# 09F-01.net
KiCad netlist of a schematic drawn in EAGLE
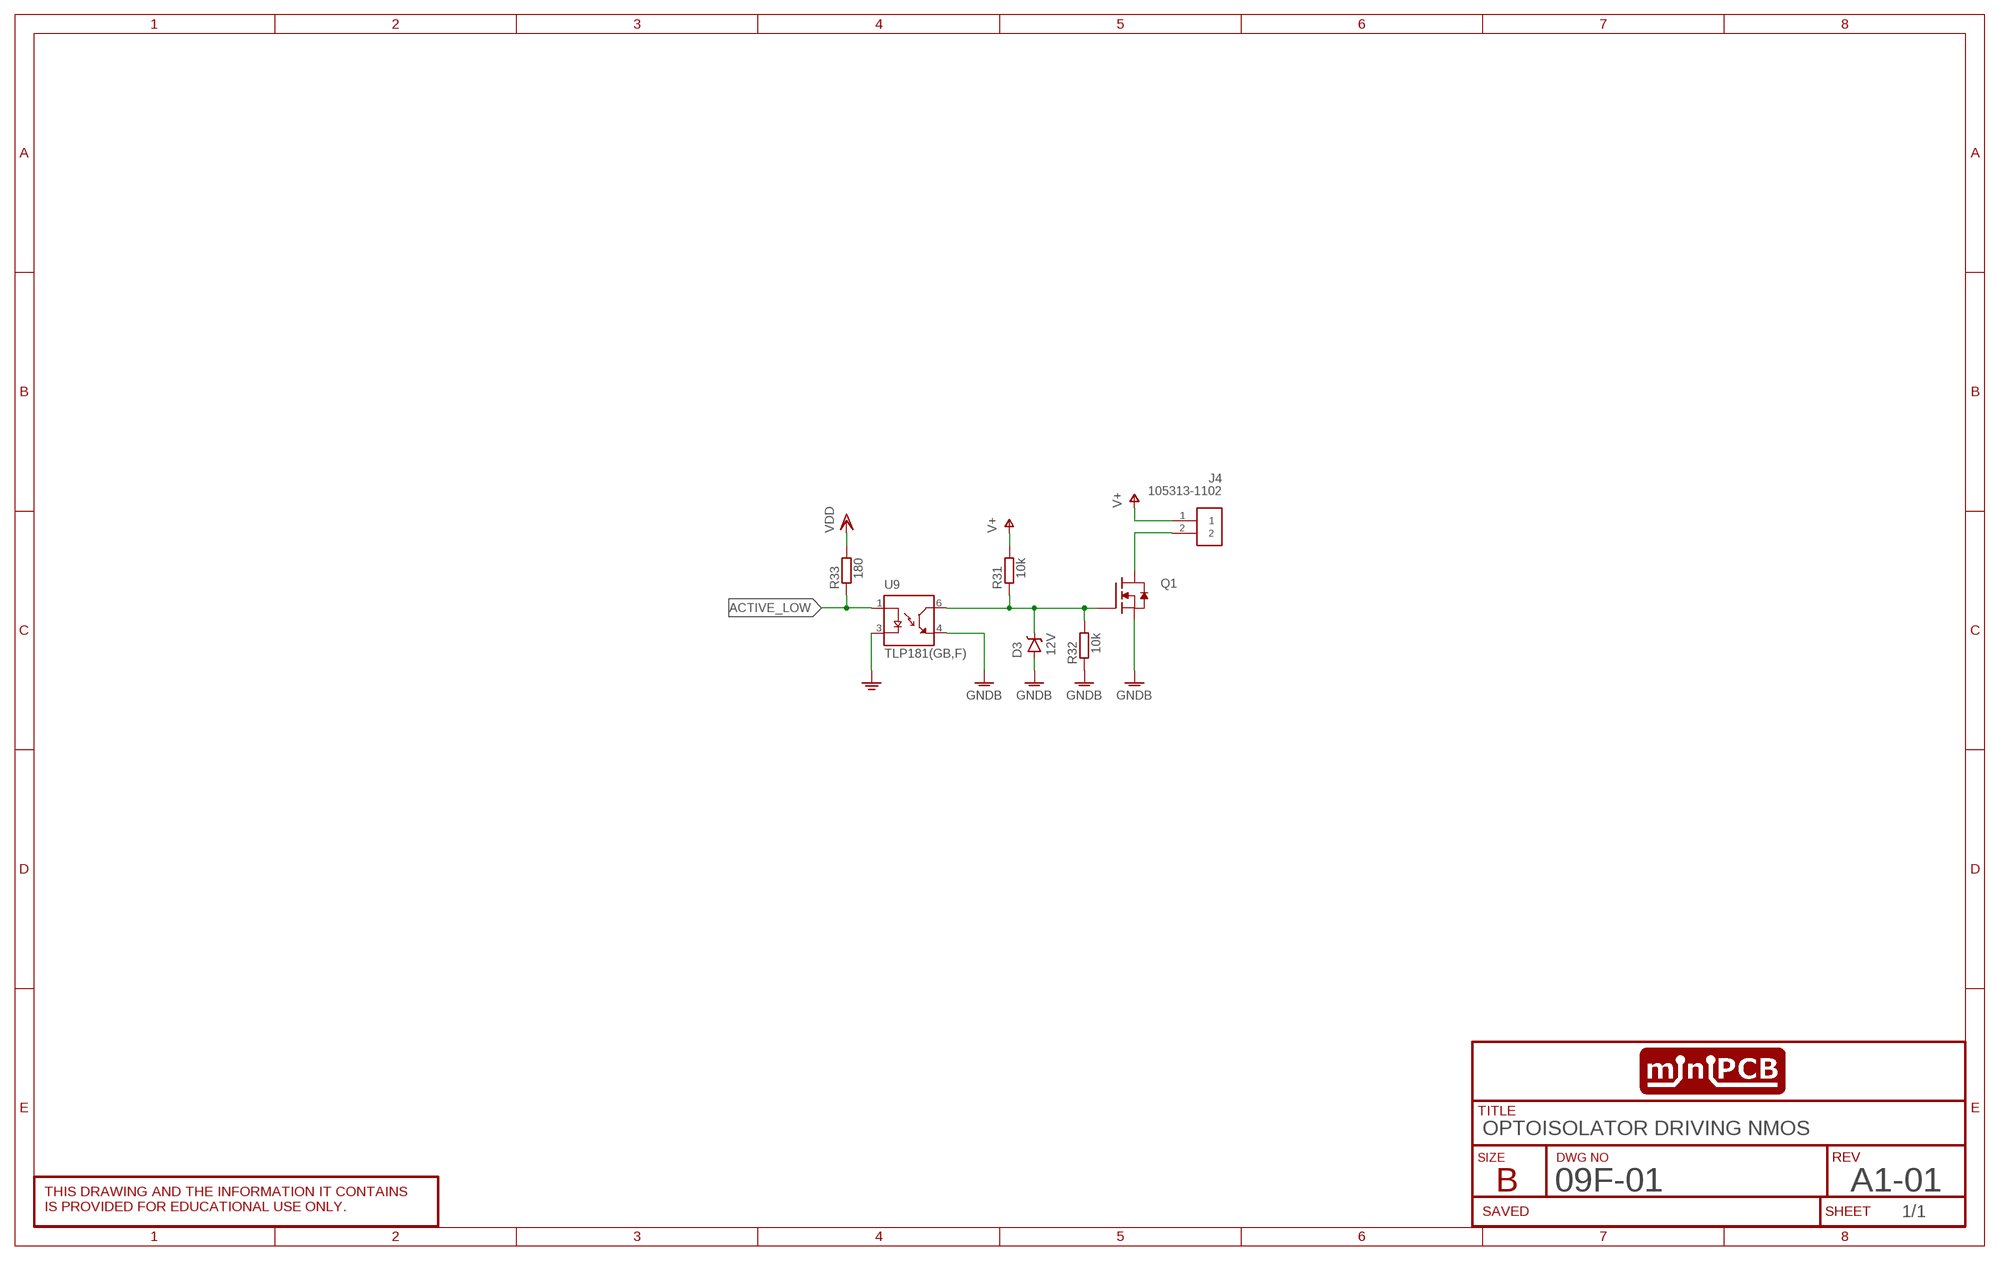
[diagram p0: schematic, sheet 1]

(export (version "E")
  (design (tool "Eeschema 10.0.6"))
  (components
    (comp (ref "D3")
      (value "12V")
      (footprint "eagle-import:SOT23")
      (libsource (lib "eagle-import") (part "ZENERSOT23"))
    )
    (comp (ref "J4")
      (value "105313-1102")
      (footprint "eagle-import:PINS_2-NANOFIT-H")
      (libsource (lib "eagle-import") (part "PINS_2-NANOFIT-105313-1102"))
    )
    (comp (ref "Q1")
      (value "MOSFET-NDPAK")
      (footprint "eagle-import:DPACK")
      (libsource (lib "eagle-import") (part "MOSFET-NDPAK"))
    )
    (comp (ref "R31")
      (value "10k")
      (footprint "eagle-import:R0805")
      (libsource (lib "eagle-import") (part "RESISTORSMD"))
    )
    (comp (ref "R32")
      (value "10k")
      (footprint "eagle-import:R0805")
      (libsource (lib "eagle-import") (part "RESISTORSMD"))
    )
    (comp (ref "R33")
      (value "180")
      (footprint "eagle-import:R0805")
      (libsource (lib "eagle-import") (part "RESISTORSMD"))
    )
    (comp (ref "U9")
      (value "TLP181(GB,F)")
      (footprint "eagle-import:SOIC254P700X280-4N")
      (fields (field (name "MF") "Toshiba"))
      (libsource (lib "eagle-import") (part "TLP181(GB,F)"))
    )
  )
  (nets
    (net (code "1") (name "ACTIVE_LOW") (class "Default")
      (node (ref "R33") (pin "1") (pinfunction "1_1") (pintype "passive"))
      (node (ref "U9") (pin "1") (pinfunction "A_1") (pintype "passive"))
    )
    (net (code "2") (name "GND") (class "Default")
      (node (ref "U9") (pin "3") (pinfunction "C_3") (pintype "passive"))
    )
    (net (code "3") (name "GNDB") (class "Default")
      (node (ref "D3") (pin "1") (pinfunction "A_1") (pintype "passive"))
      (node (ref "Q1") (pin "3") (pinfunction "S_3") (pintype "passive"))
      (node (ref "R32") (pin "1") (pinfunction "1_1") (pintype "passive"))
      (node (ref "U9") (pin "4") (pinfunction "ET_4") (pintype "passive"))
    )
    (net (code "4") (name "Net-(D3-C)") (class "Default")
      (node (ref "D3") (pin "3") (pinfunction "C_3") (pintype "passive"))
      (node (ref "Q1") (pin "1") (pinfunction "G_1") (pintype "passive"))
      (node (ref "R31") (pin "1") (pinfunction "1_1") (pintype "passive"))
      (node (ref "R32") (pin "2") (pinfunction "2_2") (pintype "passive"))
      (node (ref "U9") (pin "6") (pinfunction "CT_6") (pintype "passive"))
    )
    (net (code "5") (name "Net-(Q1-D)") (class "Default")
      (node (ref "J4") (pin "2") (pinfunction "2_2") (pintype "bidirectional"))
      (node (ref "Q1") (pin "4") (pinfunction "D_4") (pintype "passive"))
    )
    (net (code "6") (name "V+") (class "Default")
      (node (ref "J4") (pin "1") (pinfunction "1_1") (pintype "bidirectional"))
      (node (ref "R31") (pin "2") (pinfunction "2_2") (pintype "passive"))
    )
    (net (code "7") (name "VDD") (class "Default")
      (node (ref "R33") (pin "2") (pinfunction "2_2") (pintype "passive"))
    )
  )
)
